# EVK-NORA-W1_SCHEM_0001_NORA_W1_Module.net
KiCad netlist of a schematic drawn in Altium Designer
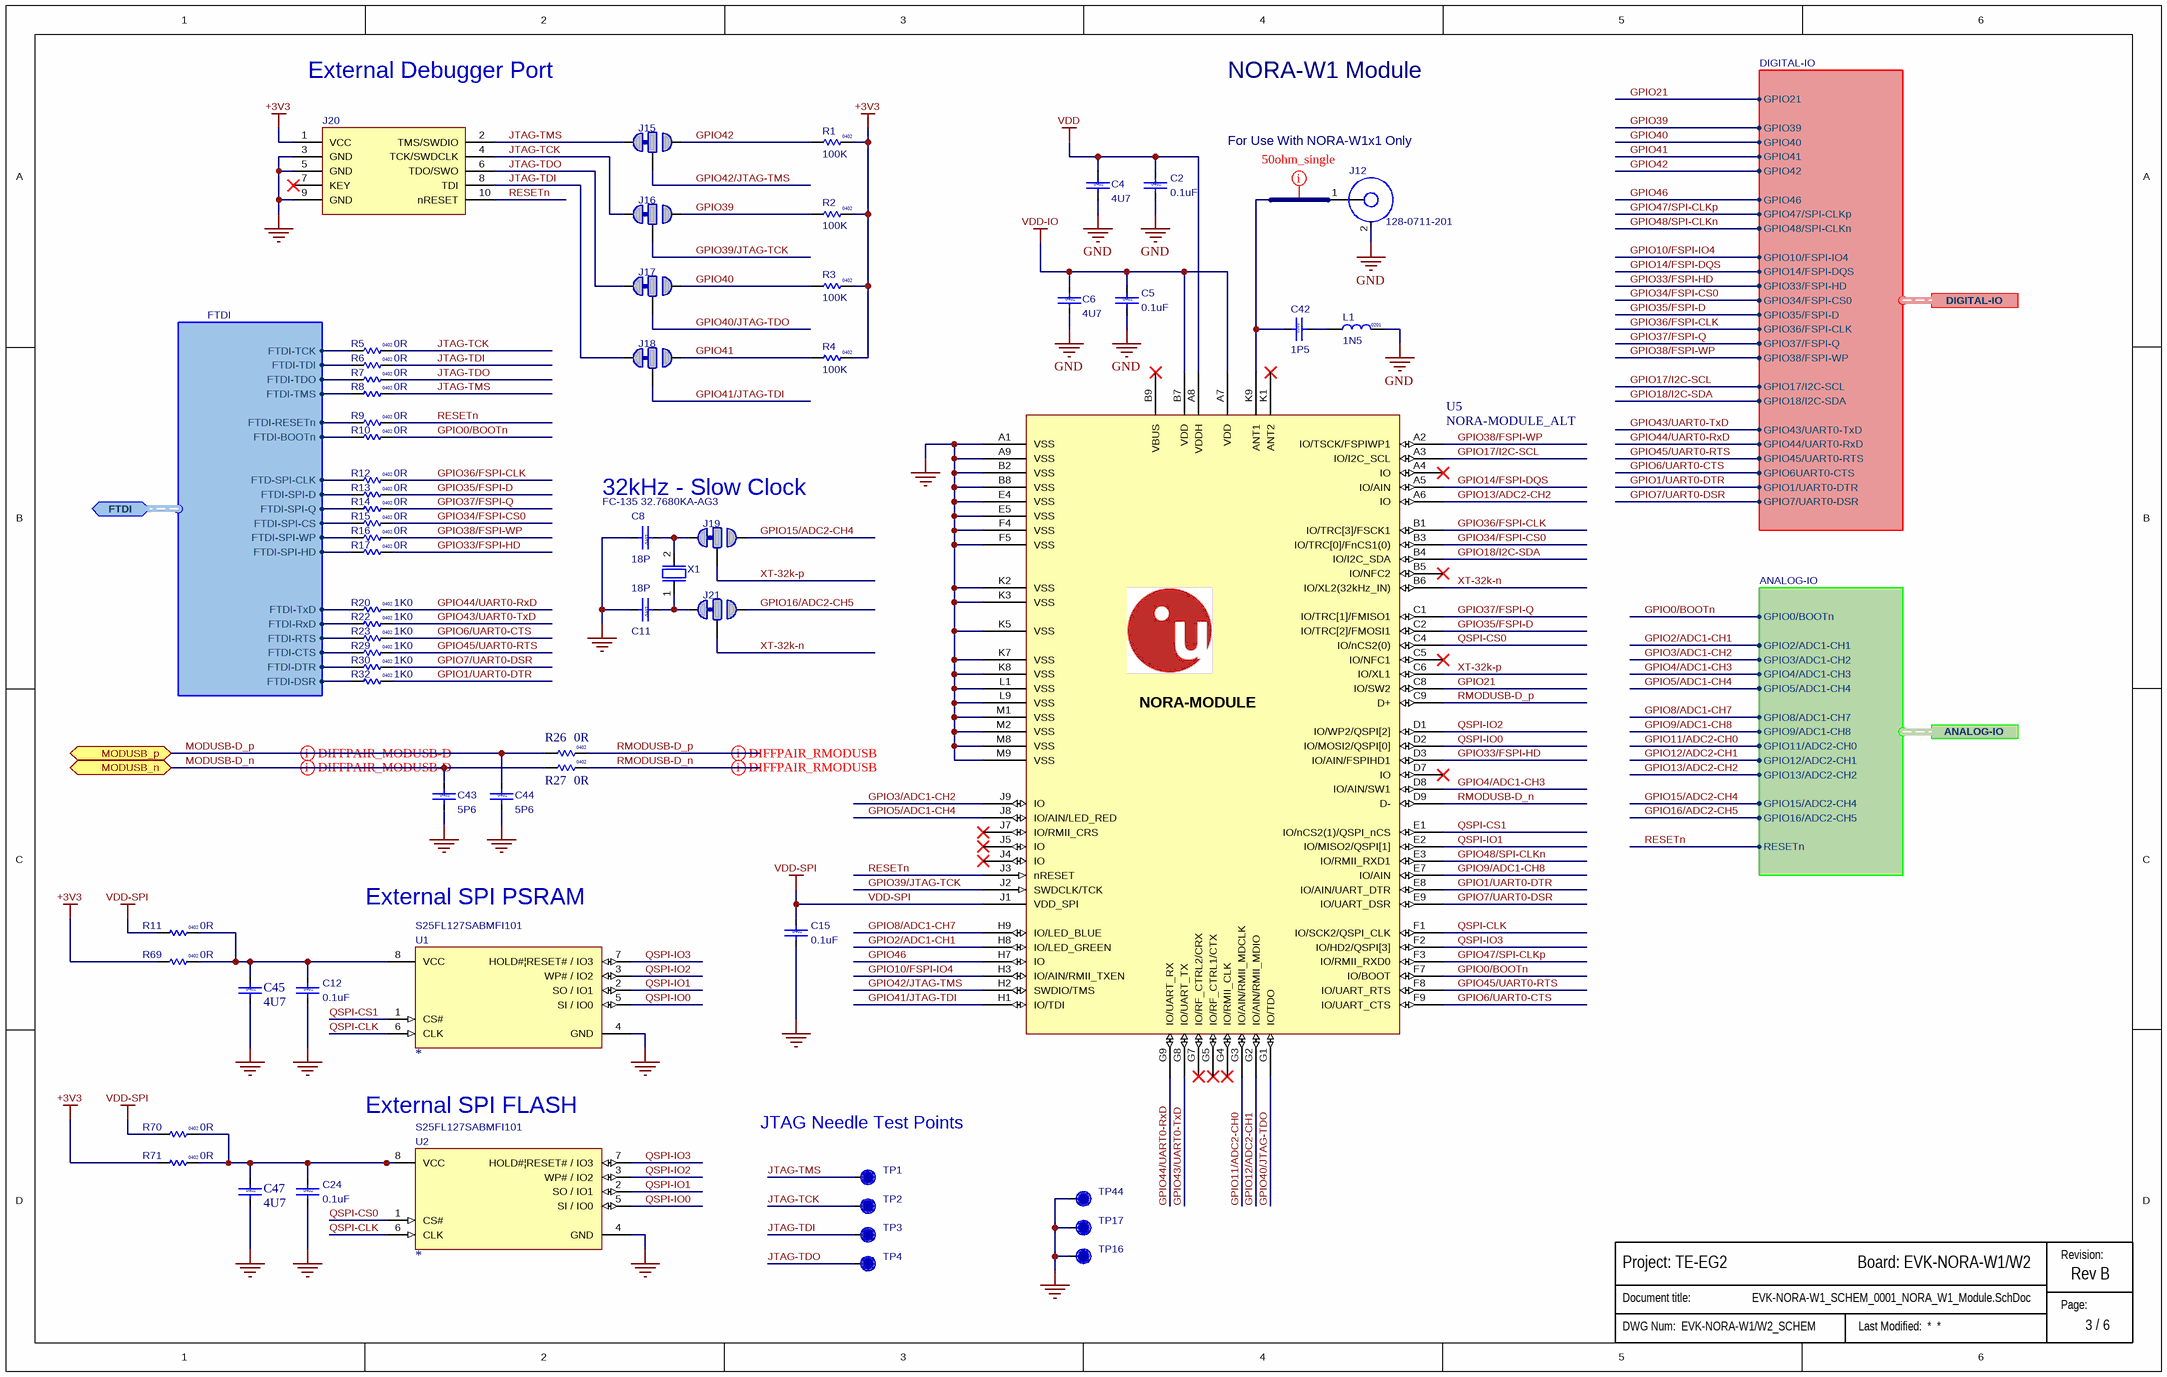
[diagram p0: EVK-NORA-W1_SCHEM_0001_NORA_W1_Module.SchDoc]

(export (version "E")
  (design (tool "Eeschema 10.0.6"))
  (components
    (comp (ref "C2")
      (value "0.1uF")
      (footprint "Cap 0402 HD")
      (description "Cap, Ceramic 0.1uF 10V 10% X5R 0402")
      (fields
        (field (name "SIZE") "0402")
        (field (name "PART NUMBER") "120-00016")
        (field (name "MANUFACTURER") "Murata Electronics North America")
      )
      (libsource (lib "Arena_Parts_DB_Lib") (part "Cap Chip"))
    )
    (comp (ref "C4")
      (value "4U7")
      (footprint "Cap 0402 HD")
      (description "CAP CER X5R 0402 4U7 20% 10V")
      (fields
        (field (name "SIZE") "0402")
        (field (name "PART NUMBER") "UBXH01-0000243")
        (field (name "TOLERANCE") "20%")
        (field (name "EDITOR") "martin.pilik")
        (field (name "RELEASED BY") "fabrice.bret-dibat")
      )
      (libsource (lib "UBX_Parts_DB_Lib") (part "Cap Chip"))
    )
    (comp (ref "C5")
      (value "0.1uF")
      (footprint "Cap 0402 HD")
      (description "Cap, Ceramic 0.1uF 10V 10% X5R 0402")
      (fields
        (field (name "SIZE") "0402")
        (field (name "PART NUMBER") "120-00016")
        (field (name "MANUFACTURER") "Murata Electronics North America")
      )
      (libsource (lib "Arena_Parts_DB_Lib") (part "Cap Chip"))
    )
    (comp (ref "C6")
      (value "4U7")
      (footprint "Cap 0402 HD")
      (description "CAP CER X5R 0402 4U7 20% 10V")
      (fields
        (field (name "SIZE") "0402")
        (field (name "PART NUMBER") "UBXH01-0000243")
        (field (name "TOLERANCE") "20%")
        (field (name "EDITOR") "martin.pilik")
        (field (name "RELEASED BY") "fabrice.bret-dibat")
      )
      (libsource (lib "UBX_Parts_DB_Lib") (part "Cap Chip"))
    )
    (comp (ref "C8")
      (value "18P")
      (footprint "Cap 0402")
      (description "CAP CER C0G 0402 18P 5% 25V")
      (fields
        (field (name "SIZE") "0402")
        (field (name "PART NUMBER") "UBXH01-0004017")
        (field (name "TOLERANCE") "5%")
        (field (name "EDITOR") "doris.zahnd")
        (field (name "RELEASED BY") "daniel.hurni")
      )
      (libsource (lib "UBX_Parts_DB_Lib") (part "Cap Chip"))
    )
    (comp (ref "C11")
      (value "18P")
      (footprint "Cap 0402")
      (description "CAP CER C0G 0402 18P 5% 25V")
      (fields
        (field (name "SIZE") "0402")
        (field (name "PART NUMBER") "UBXH01-0004017")
        (field (name "TOLERANCE") "5%")
        (field (name "EDITOR") "doris.zahnd")
        (field (name "RELEASED BY") "daniel.hurni")
      )
      (libsource (lib "UBX_Parts_DB_Lib") (part "Cap Chip"))
    )
    (comp (ref "C12")
      (value "0.1uF")
      (footprint "Cap 0402 HD")
      (description "Cap, Ceramic 0.1uF 10V 10% X5R 0402")
      (fields
        (field (name "SIZE") "0402")
        (field (name "PART NUMBER") "120-00016")
        (field (name "MANUFACTURER") "Murata Electronics North America")
      )
      (libsource (lib "Arena_Parts_DB_Lib") (part "Cap Chip"))
    )
    (comp (ref "C15")
      (value "0.1uF")
      (footprint "Cap 0402 HD")
      (description "Cap, Ceramic 0.1uF 10V 10% X5R 0402")
      (fields
        (field (name "SIZE") "0402")
        (field (name "PART NUMBER") "120-00016")
        (field (name "MANUFACTURER") "Murata Electronics North America")
      )
      (libsource (lib "Arena_Parts_DB_Lib") (part "Cap Chip"))
    )
    (comp (ref "C24")
      (value "0.1uF")
      (footprint "Cap 0402 HD")
      (description "Cap, Ceramic 0.1uF 10V 10% X5R 0402")
      (fields
        (field (name "SIZE") "0402")
        (field (name "PART NUMBER") "120-00016")
        (field (name "MANUFACTURER") "Murata Electronics North America")
      )
      (libsource (lib "Arena_Parts_DB_Lib") (part "Cap Chip"))
    )
    (comp (ref "C42")
      (value "1P5")
      (footprint "Cap 0201 HD")
      (description "CAP CER C0G 0201 1P5 +/-0.25P 25V")
      (fields
        (field (name "SIZE") "0201")
        (field (name "PART NUMBER") "UBXH01-0012002")
        (field (name "TOLERANCE") "+/-0.25P")
        (field (name "EDITOR") "roland.rust")
        (field (name "RELEASED BY") "roland.rust")
      )
      (libsource (lib "UBX_Parts_DB_Lib") (part "Cap Chip"))
    )
    (comp (ref "C43")
      (value "5P6")
      (footprint "Cap 0402")
      (description "CAP CER C0G 0402 5P6 +/-0.25P 25V")
      (fields
        (field (name "SIZE") "0402")
        (field (name "PART NUMBER") "UBXH01-0004011")
        (field (name "TOLERANCE") "+/-0.25P")
        (field (name "EDITOR") "roland.rust")
        (field (name "RELEASED BY") "roland.rust")
      )
      (libsource (lib "UBX_Parts_DB_Lib") (part "Cap Chip"))
    )
    (comp (ref "C44")
      (value "5P6")
      (footprint "Cap 0402")
      (description "CAP CER C0G 0402 5P6 +/-0.25P 25V")
      (fields
        (field (name "SIZE") "0402")
        (field (name "PART NUMBER") "UBXH01-0004011")
        (field (name "TOLERANCE") "+/-0.25P")
        (field (name "EDITOR") "roland.rust")
        (field (name "RELEASED BY") "roland.rust")
      )
      (libsource (lib "UBX_Parts_DB_Lib") (part "Cap Chip"))
    )
    (comp (ref "C45")
      (value "4U7")
      (footprint "Cap 0402 HD")
      (description "CAP CER X5R 0402 4U7 20% 10V")
      (fields
        (field (name "SIZE") "0402")
        (field (name "PART NUMBER") "UBXH01-0000243")
        (field (name "TOLERANCE") "20%")
        (field (name "EDITOR") "martin.pilik")
        (field (name "RELEASED BY") "fabrice.bret-dibat")
      )
      (libsource (lib "UBX_Parts_DB_Lib") (part "Cap Chip"))
    )
    (comp (ref "C47")
      (value "4U7")
      (footprint "Cap 0402 HD")
      (description "CAP CER X5R 0402 4U7 20% 10V")
      (fields
        (field (name "SIZE") "0402")
        (field (name "PART NUMBER") "UBXH01-0000243")
        (field (name "TOLERANCE") "20%")
        (field (name "EDITOR") "martin.pilik")
        (field (name "RELEASED BY") "fabrice.bret-dibat")
      )
      (libsource (lib "UBX_Parts_DB_Lib") (part "Cap Chip"))
    )
    (comp (ref "J12")
      (value "130-00067")
      (footprint "U.FL_3Pin")
      (description "U.FL jack, SMA 50 ohm, 3 pin, SMT")
      (fields
        (field (name "MANUFACTURER P/N") "128-0711-201")
        (field (name "MANUFACTURER") "Cinch Connectivity")
      )
      (libsource (lib "Arena_Parts_DB_Lib") (part "CON_Coax_2Pin"))
    )
    (comp (ref "J15")
      (value "Solderbridge-OptionDNP")
      (footprint "Solderbridge-Option")
      (description "Solderbridge-Option")
      (fields (field (name "ADDED BY") "Paul B"))
      (libsource (lib "LEGACY_Rigado_AltiumLib") (part "Solderbridge-Option"))
    )
    (comp (ref "J16")
      (value "Solderbridge-OptionDNP")
      (footprint "Solderbridge-Option")
      (description "Solderbridge-Option")
      (fields (field (name "ADDED BY") "Paul B"))
      (libsource (lib "LEGACY_Rigado_AltiumLib") (part "Solderbridge-Option"))
    )
    (comp (ref "J17")
      (value "Solderbridge-OptionDNP")
      (footprint "Solderbridge-Option")
      (description "Solderbridge-Option")
      (fields (field (name "ADDED BY") "Paul B"))
      (libsource (lib "LEGACY_Rigado_AltiumLib") (part "Solderbridge-Option"))
    )
    (comp (ref "J18")
      (value "Solderbridge-OptionDNP")
      (footprint "Solderbridge-Option")
      (description "Solderbridge-Option")
      (fields (field (name "ADDED BY") "Paul B"))
      (libsource (lib "LEGACY_Rigado_AltiumLib") (part "Solderbridge-Option"))
    )
    (comp (ref "J19")
      (value "Solderbridge-OptionDNP")
      (footprint "Solderbridge-Option")
      (description "Solderbridge-Option")
      (fields (field (name "ADDED BY") "Paul B"))
      (libsource (lib "LEGACY_Rigado_AltiumLib") (part "Solderbridge-Option"))
    )
    (comp (ref "J20")
      (value "130-00099")
      (footprint "HDR.050P-10Pin-2x5-SMT_Key")
      (description "Header 0.05\" 10Pin 2Row SMD Black")
      (fields (field (name "MANUFACTURER") "Samtec"))
      (libsource (lib "Arena_Parts_DB_Lib") (part "JTAG-10Pin"))
    )
    (comp (ref "J21")
      (value "Solderbridge-OptionDNP")
      (footprint "Solderbridge-Option")
      (description "Solderbridge-Option")
      (fields (field (name "ADDED BY") "Paul B"))
      (libsource (lib "LEGACY_Rigado_AltiumLib") (part "Solderbridge-Option"))
    )
    (comp (ref "L1")
      (value "1N5")
      (footprint "IND 0201 HD")
      (description "IND MURATA LQP03T_02 0201 1N5 +/-0.1N 600mA")
      (fields
        (field (name "SIZE") "0201")
        (field (name "PART NUMBER") "UBXH09-0000030")
        (field (name "TOLERANCE") "+/-0.1N")
        (field (name "EDITOR") "massimo.pros")
        (field (name "RELEASED BY") "massimo.vlacci")
      )
      (libsource (lib "UBX_Parts_DB_Lib") (part "Ind sm"))
    )
    (comp (ref "R1")
      (value "100K")
      (footprint "RES 0402 HD")
      (description "RES THICK FILM CHIP 0402 100K 5% 100mW")
      (fields
        (field (name "SIZE") "0402")
        (field (name "PART NUMBER") "UBXH18-0008097")
        (field (name "TOLERANCE") "5%")
        (field (name "EDITOR") "roland.rust")
        (field (name "RELEASED BY") "roland.rust")
      )
      (libsource (lib "UBX_Parts_DB_Lib") (part "Res sm"))
    )
    (comp (ref "R2")
      (value "100K")
      (footprint "RES 0402 HD")
      (description "RES THICK FILM CHIP 0402 100K 5% 100mW")
      (fields
        (field (name "SIZE") "0402")
        (field (name "PART NUMBER") "UBXH18-0008097")
        (field (name "TOLERANCE") "5%")
        (field (name "EDITOR") "roland.rust")
        (field (name "RELEASED BY") "roland.rust")
      )
      (libsource (lib "UBX_Parts_DB_Lib") (part "Res sm"))
    )
    (comp (ref "R3")
      (value "100K")
      (footprint "RES 0402 HD")
      (description "RES THICK FILM CHIP 0402 100K 5% 100mW")
      (fields
        (field (name "SIZE") "0402")
        (field (name "PART NUMBER") "UBXH18-0008097")
        (field (name "TOLERANCE") "5%")
        (field (name "EDITOR") "roland.rust")
        (field (name "RELEASED BY") "roland.rust")
      )
      (libsource (lib "UBX_Parts_DB_Lib") (part "Res sm"))
    )
    (comp (ref "R4")
      (value "100K")
      (footprint "RES 0402 HD")
      (description "RES THICK FILM CHIP 0402 100K 5% 100mW")
      (fields
        (field (name "SIZE") "0402")
        (field (name "PART NUMBER") "UBXH18-0008097")
        (field (name "TOLERANCE") "5%")
        (field (name "EDITOR") "roland.rust")
        (field (name "RELEASED BY") "roland.rust")
      )
      (libsource (lib "UBX_Parts_DB_Lib") (part "Res sm"))
    )
    (comp (ref "R5")
      (value "0R")
      (footprint "RES 0402 HD")
      (description "RES THICK FILM CHIP 0402 0R 0 100mW")
      (fields
        (field (name "SIZE") "0402")
        (field (name "PART NUMBER") "UBXH18-0003002")
        (field (name "TOLERANCE") "0")
        (field (name "EDITOR") "charlotte.biber")
        (field (name "RELEASED BY") "peter.mueller")
      )
      (libsource (lib "UBX_Parts_DB_Lib") (part "Res sm"))
    )
    (comp (ref "R6")
      (value "0R")
      (footprint "RES 0402 HD")
      (description "RES THICK FILM CHIP 0402 0R 0 100mW")
      (fields
        (field (name "SIZE") "0402")
        (field (name "PART NUMBER") "UBXH18-0003002")
        (field (name "TOLERANCE") "0")
        (field (name "EDITOR") "charlotte.biber")
        (field (name "RELEASED BY") "peter.mueller")
      )
      (libsource (lib "UBX_Parts_DB_Lib") (part "Res sm"))
    )
    (comp (ref "R7")
      (value "0R")
      (footprint "RES 0402 HD")
      (description "RES THICK FILM CHIP 0402 0R 0 100mW")
      (fields
        (field (name "SIZE") "0402")
        (field (name "PART NUMBER") "UBXH18-0003002")
        (field (name "TOLERANCE") "0")
        (field (name "EDITOR") "charlotte.biber")
        (field (name "RELEASED BY") "peter.mueller")
      )
      (libsource (lib "UBX_Parts_DB_Lib") (part "Res sm"))
    )
    (comp (ref "R8")
      (value "0R")
      (footprint "RES 0402 HD")
      (description "RES THICK FILM CHIP 0402 0R 0 100mW")
      (fields
        (field (name "SIZE") "0402")
        (field (name "PART NUMBER") "UBXH18-0003002")
        (field (name "TOLERANCE") "0")
        (field (name "EDITOR") "charlotte.biber")
        (field (name "RELEASED BY") "peter.mueller")
      )
      (libsource (lib "UBX_Parts_DB_Lib") (part "Res sm"))
    )
    (comp (ref "R9")
      (value "0R")
      (footprint "RES 0402 HD")
      (description "RES THICK FILM CHIP 0402 0R 0 100mW")
      (fields
        (field (name "SIZE") "0402")
        (field (name "PART NUMBER") "UBXH18-0003002")
        (field (name "TOLERANCE") "0")
        (field (name "EDITOR") "charlotte.biber")
        (field (name "RELEASED BY") "peter.mueller")
      )
      (libsource (lib "UBX_Parts_DB_Lib") (part "Res sm"))
    )
    (comp (ref "R10")
      (value "0R")
      (footprint "RES 0402 HD")
      (description "RES THICK FILM CHIP 0402 0R 0 100mW")
      (fields
        (field (name "SIZE") "0402")
        (field (name "PART NUMBER") "UBXH18-0003002")
        (field (name "TOLERANCE") "0")
        (field (name "EDITOR") "charlotte.biber")
        (field (name "RELEASED BY") "peter.mueller")
      )
      (libsource (lib "UBX_Parts_DB_Lib") (part "Res sm"))
    )
    (comp (ref "R11")
      (value "0R")
      (footprint "RES 0402 HD")
      (description "RES THICK FILM CHIP 0402 0R 0 100mW")
      (fields
        (field (name "SIZE") "0402")
        (field (name "PART NUMBER") "UBXH18-0003002")
        (field (name "TOLERANCE") "0")
        (field (name "EDITOR") "charlotte.biber")
        (field (name "RELEASED BY") "peter.mueller")
      )
      (libsource (lib "UBX_Parts_DB_Lib") (part "Res sm"))
    )
    (comp (ref "R12")
      (value "0R")
      (footprint "RES 0402 HD")
      (description "RES THICK FILM CHIP 0402 0R 0 100mW")
      (fields
        (field (name "SIZE") "0402")
        (field (name "PART NUMBER") "UBXH18-0003002")
        (field (name "TOLERANCE") "0")
        (field (name "EDITOR") "charlotte.biber")
        (field (name "RELEASED BY") "peter.mueller")
      )
      (libsource (lib "UBX_Parts_DB_Lib") (part "Res sm"))
    )
    (comp (ref "R13")
      (value "0R")
      (footprint "RES 0402 HD")
      (description "RES THICK FILM CHIP 0402 0R 0 100mW")
      (fields
        (field (name "SIZE") "0402")
        (field (name "PART NUMBER") "UBXH18-0003002")
        (field (name "TOLERANCE") "0")
        (field (name "EDITOR") "charlotte.biber")
        (field (name "RELEASED BY") "peter.mueller")
      )
      (libsource (lib "UBX_Parts_DB_Lib") (part "Res sm"))
    )
    (comp (ref "R14")
      (value "0R")
      (footprint "RES 0402 HD")
      (description "RES THICK FILM CHIP 0402 0R 0 100mW")
      (fields
        (field (name "SIZE") "0402")
        (field (name "PART NUMBER") "UBXH18-0003002")
        (field (name "TOLERANCE") "0")
        (field (name "EDITOR") "charlotte.biber")
        (field (name "RELEASED BY") "peter.mueller")
      )
      (libsource (lib "UBX_Parts_DB_Lib") (part "Res sm"))
    )
    (comp (ref "R15")
      (value "0R")
      (footprint "RES 0402 HD")
      (description "RES THICK FILM CHIP 0402 0R 0 100mW")
      (fields
        (field (name "SIZE") "0402")
        (field (name "PART NUMBER") "UBXH18-0003002")
        (field (name "TOLERANCE") "0")
        (field (name "EDITOR") "charlotte.biber")
        (field (name "RELEASED BY") "peter.mueller")
      )
      (libsource (lib "UBX_Parts_DB_Lib") (part "Res sm"))
    )
    (comp (ref "R16")
      (value "0R")
      (footprint "RES 0402 HD")
      (description "RES THICK FILM CHIP 0402 0R 0 100mW")
      (fields
        (field (name "SIZE") "0402")
        (field (name "PART NUMBER") "UBXH18-0003002")
        (field (name "TOLERANCE") "0")
        (field (name "EDITOR") "charlotte.biber")
        (field (name "RELEASED BY") "peter.mueller")
      )
      (libsource (lib "UBX_Parts_DB_Lib") (part "Res sm"))
    )
    (comp (ref "R17")
      (value "0R")
      (footprint "RES 0402 HD")
      (description "RES THICK FILM CHIP 0402 0R 0 100mW")
      (fields
        (field (name "SIZE") "0402")
        (field (name "PART NUMBER") "UBXH18-0003002")
        (field (name "TOLERANCE") "0")
        (field (name "EDITOR") "charlotte.biber")
        (field (name "RELEASED BY") "peter.mueller")
      )
      (libsource (lib "UBX_Parts_DB_Lib") (part "Res sm"))
    )
    (comp (ref "R20")
      (value "1K0")
      (footprint "RES 0402 HD")
      (description "RES THICK FILM CHIP 0402 1K0 5% 100mW")
      (fields
        (field (name "SIZE") "0402")
        (field (name "PART NUMBER") "UBXH18-0008049")
        (field (name "TOLERANCE") "5%")
        (field (name "EDITOR") "roland.rust")
        (field (name "RELEASED BY") "roland.rust")
      )
      (libsource (lib "UBX_Parts_DB_Lib") (part "Res sm"))
    )
    (comp (ref "R22")
      (value "1K0")
      (footprint "RES 0402 HD")
      (description "RES THICK FILM CHIP 0402 1K0 5% 100mW")
      (fields
        (field (name "SIZE") "0402")
        (field (name "PART NUMBER") "UBXH18-0008049")
        (field (name "TOLERANCE") "5%")
        (field (name "EDITOR") "roland.rust")
        (field (name "RELEASED BY") "roland.rust")
      )
      (libsource (lib "UBX_Parts_DB_Lib") (part "Res sm"))
    )
    (comp (ref "R23")
      (value "1K0")
      (footprint "RES 0402 HD")
      (description "RES THICK FILM CHIP 0402 1K0 5% 100mW")
      (fields
        (field (name "SIZE") "0402")
        (field (name "PART NUMBER") "UBXH18-0008049")
        (field (name "TOLERANCE") "5%")
        (field (name "EDITOR") "roland.rust")
        (field (name "RELEASED BY") "roland.rust")
      )
      (libsource (lib "UBX_Parts_DB_Lib") (part "Res sm"))
    )
    (comp (ref "R26")
      (value "0R")
      (footprint "RES 0402 HD")
      (description "RES THICK FILM CHIP 0402 0R 0 100mW")
      (fields
        (field (name "SIZE") "0402")
        (field (name "PART NUMBER") "UBXH18-0003002")
        (field (name "TOLERANCE") "0")
        (field (name "EDITOR") "charlotte.biber")
        (field (name "RELEASED BY") "peter.mueller")
      )
      (libsource (lib "UBX_Parts_DB_Lib") (part "Res sm"))
    )
    (comp (ref "R27")
      (value "0R")
      (footprint "RES 0402 HD")
      (description "RES THICK FILM CHIP 0402 0R 0 100mW")
      (fields
        (field (name "SIZE") "0402")
        (field (name "PART NUMBER") "UBXH18-0003002")
        (field (name "TOLERANCE") "0")
        (field (name "EDITOR") "charlotte.biber")
        (field (name "RELEASED BY") "peter.mueller")
      )
      (libsource (lib "UBX_Parts_DB_Lib") (part "Res sm"))
    )
    (comp (ref "R29")
      (value "1K0")
      (footprint "RES 0402 HD")
      (description "RES THICK FILM CHIP 0402 1K0 5% 100mW")
      (fields
        (field (name "SIZE") "0402")
        (field (name "PART NUMBER") "UBXH18-0008049")
        (field (name "TOLERANCE") "5%")
        (field (name "EDITOR") "roland.rust")
        (field (name "RELEASED BY") "roland.rust")
      )
      (libsource (lib "UBX_Parts_DB_Lib") (part "Res sm"))
    )
    (comp (ref "R30")
      (value "1K0")
      (footprint "RES 0402 HD")
      (description "RES THICK FILM CHIP 0402 1K0 5% 100mW")
      (fields
        (field (name "SIZE") "0402")
        (field (name "PART NUMBER") "UBXH18-0008049")
        (field (name "TOLERANCE") "5%")
        (field (name "EDITOR") "roland.rust")
        (field (name "RELEASED BY") "roland.rust")
      )
      (libsource (lib "UBX_Parts_DB_Lib") (part "Res sm"))
    )
    (comp (ref "R32")
      (value "1K0")
      (footprint "RES 0402 HD")
      (description "RES THICK FILM CHIP 0402 1K0 5% 100mW")
      (fields
        (field (name "SIZE") "0402")
        (field (name "PART NUMBER") "UBXH18-0008049")
        (field (name "TOLERANCE") "5%")
        (field (name "EDITOR") "roland.rust")
        (field (name "RELEASED BY") "roland.rust")
      )
      (libsource (lib "UBX_Parts_DB_Lib") (part "Res sm"))
    )
    (comp (ref "R69")
      (value "0R")
      (footprint "RES 0402 HD")
      (description "RES THICK FILM CHIP 0402 0R 0 100mW")
      (fields
        (field (name "SIZE") "0402")
        (field (name "PART NUMBER") "UBXH18-0003002")
        (field (name "TOLERANCE") "0")
        (field (name "EDITOR") "charlotte.biber")
        (field (name "RELEASED BY") "peter.mueller")
      )
      (libsource (lib "UBX_Parts_DB_Lib") (part "Res sm"))
    )
    (comp (ref "R70")
      (value "0R")
      (footprint "RES 0402 HD")
      (description "RES THICK FILM CHIP 0402 0R 0 100mW")
      (fields
        (field (name "SIZE") "0402")
        (field (name "PART NUMBER") "UBXH18-0003002")
        (field (name "TOLERANCE") "0")
        (field (name "EDITOR") "charlotte.biber")
        (field (name "RELEASED BY") "peter.mueller")
      )
      (libsource (lib "UBX_Parts_DB_Lib") (part "Res sm"))
    )
    (comp (ref "R71")
      (value "0R")
      (footprint "RES 0402 HD")
      (description "RES THICK FILM CHIP 0402 0R 0 100mW")
      (fields
        (field (name "SIZE") "0402")
        (field (name "PART NUMBER") "UBXH18-0003002")
        (field (name "TOLERANCE") "0")
        (field (name "EDITOR") "charlotte.biber")
        (field (name "RELEASED BY") "peter.mueller")
      )
      (libsource (lib "UBX_Parts_DB_Lib") (part "Res sm"))
    )
    (comp (ref "TP1")
      (value "TP")
      (footprint "TP10R")
      (description "Testpoint, Round 1.0mm Dia")
      (fields
        (field (name "PART NUMBER") "TP10R")
        (field (name "ADDED BY") "Jeremy D")
        (field (name "CHECKED BY") "Paul B")
      )
      (libsource (lib "LEGACY_Rigado_AltiumLib") (part "TP_R"))
    )
    (comp (ref "TP2")
      (value "TP")
      (footprint "TP10R")
      (description "Testpoint, Round 1.0mm Dia")
      (fields
        (field (name "PART NUMBER") "TP10R")
        (field (name "ADDED BY") "Jeremy D")
        (field (name "CHECKED BY") "Paul B")
      )
      (libsource (lib "LEGACY_Rigado_AltiumLib") (part "TP_R"))
    )
    (comp (ref "TP3")
      (value "TP")
      (footprint "TP10R")
      (description "Testpoint, Round 1.0mm Dia")
      (fields
        (field (name "PART NUMBER") "TP10R")
        (field (name "ADDED BY") "Jeremy D")
        (field (name "CHECKED BY") "Paul B")
      )
      (libsource (lib "LEGACY_Rigado_AltiumLib") (part "TP_R"))
    )
    (comp (ref "TP4")
      (value "TP")
      (footprint "TP10R")
      (description "Testpoint, Round 1.0mm Dia")
      (fields
        (field (name "PART NUMBER") "TP10R")
        (field (name "ADDED BY") "Jeremy D")
        (field (name "CHECKED BY") "Paul B")
      )
      (libsource (lib "LEGACY_Rigado_AltiumLib") (part "TP_R"))
    )
    (comp (ref "TP16")
      (value "TP")
      (footprint "TP10R")
      (description "Testpoint, Round 1.0mm Dia")
      (fields
        (field (name "PART NUMBER") "TP10R")
        (field (name "ADDED BY") "Jeremy D")
        (field (name "CHECKED BY") "Paul B")
      )
      (libsource (lib "LEGACY_Rigado_AltiumLib") (part "TP_R"))
    )
    (comp (ref "TP17")
      (value "TP")
      (footprint "TP10R")
      (description "Testpoint, Round 1.0mm Dia")
      (fields
        (field (name "PART NUMBER") "TP10R")
        (field (name "ADDED BY") "Jeremy D")
        (field (name "CHECKED BY") "Paul B")
      )
      (libsource (lib "LEGACY_Rigado_AltiumLib") (part "TP_R"))
    )
    (comp (ref "TP44")
      (value "TP")
      (footprint "TP10R")
      (description "Testpoint, Round 1.0mm Dia")
      (fields
        (field (name "PART NUMBER") "TP10R")
        (field (name "ADDED BY") "Jeremy D")
        (field (name "CHECKED BY") "Paul B")
      )
      (libsource (lib "LEGACY_Rigado_AltiumLib") (part "TP_R"))
    )
    (comp (ref "U1")
      (value "240-00017")
      (footprint "SOIC-8W")
      (description "IC, Flash 128MBIT, 108MHz, 8SOIC")
      (fields
        (field (name "MANUFACTURER P/N") "*")
        (field (name "MANUFACTURER PART NUMBER 1") "S25FL127SABMFI101")
        (field (name "VOLTAGE") "3.6V")
      )
      (libsource (lib "Arena_Parts_DB_Lib") (part "SPI_Flash_Memory_8Pin"))
    )
    (comp (ref "U2")
      (value "240-00017")
      (footprint "SOIC-8W")
      (description "IC, Flash 128MBIT, 108MHz, 8SOIC")
      (fields
        (field (name "MANUFACTURER P/N") "*")
        (field (name "MANUFACTURER PART NUMBER 1") "S25FL127SABMFI101")
        (field (name "VOLTAGE") "3.6V")
      )
      (libsource (lib "Arena_Parts_DB_Lib") (part "SPI_Flash_Memory_8Pin"))
    )
    (comp (ref "U5")
      (value "NORA-MODULE_ALT")
      (footprint "NORA:NORA_LGA82R_1430X1040X180_ANT")
      (description "u-blox NORA module generic symbol for use within module designs - alternate version")
      (fields (field (name "PART NUMBER") "NORA") (field (name "MANUFACTURER") "u-blox"))
      (libsource (lib "NORA") (part "NORA-MODULE_ALT"))
    )
    (comp (ref "X1")
      (value "100-00005")
      (footprint "XTAL_3215")
      (description "XTAL, 2Pin, 32.768kHz, 7pF 20ppm")
      (fields (field (name "MANUFACTURER P/N") "FC-135 32.7680KA-AG3") (field (name "MANUFACTURER") "Epson"))
      (libsource (lib "Arena_Parts_DB_Lib") (part "XTAL_2Pin"))
    )
  )
  (nets
    (net (code "4") (name "+3V3") (class "Default")
      (node (ref "J20") (pin "1") (pinfunction "VCC_1") (pintype "passive"))
      (node (ref "R1") (pin "2") (pinfunction "2_2") (pintype "passive"))
      (node (ref "R2") (pin "2") (pinfunction "2_2") (pintype "passive"))
      (node (ref "R3") (pin "2") (pinfunction "2_2") (pintype "passive"))
      (node (ref "R4") (pin "2") (pinfunction "2_2") (pintype "passive"))
      (node (ref "R69") (pin "1") (pinfunction "1_1") (pintype "passive"))
      (node (ref "R71") (pin "1") (pinfunction "1_1") (pintype "passive"))
    )
    (net (code "5") (name "/FTD-SPI-CLK") (class "Default")
      (node (ref "R12") (pin "1") (pinfunction "1_1") (pintype "passive"))
    )
    (net (code "6") (name "/FTDI-BOOTn") (class "Default")
      (node (ref "R10") (pin "1") (pinfunction "1_1") (pintype "passive"))
    )
    (net (code "7") (name "/FTDI-CTS") (class "Default")
      (node (ref "R29") (pin "1") (pinfunction "1_1") (pintype "passive"))
    )
    (net (code "8") (name "/FTDI-DSR") (class "Default")
      (node (ref "R32") (pin "1") (pinfunction "1_1") (pintype "passive"))
    )
    (net (code "9") (name "/FTDI-DTR") (class "Default")
      (node (ref "R30") (pin "1") (pinfunction "1_1") (pintype "passive"))
    )
    (net (code "10") (name "/FTDI-RESETn") (class "Default")
      (node (ref "R9") (pin "1") (pinfunction "1_1") (pintype "passive"))
    )
    (net (code "11") (name "/FTDI-RTS") (class "Default")
      (node (ref "R23") (pin "1") (pinfunction "1_1") (pintype "passive"))
    )
    (net (code "12") (name "/FTDI-RxD") (class "Default")
      (node (ref "R22") (pin "1") (pinfunction "1_1") (pintype "passive"))
    )
    (net (code "13") (name "/FTDI-SPI-CS") (class "Default")
      (node (ref "R15") (pin "1") (pinfunction "1_1") (pintype "passive"))
    )
    (net (code "14") (name "/FTDI-SPI-D") (class "Default")
      (node (ref "R13") (pin "1") (pinfunction "1_1") (pintype "passive"))
    )
    (net (code "15") (name "/FTDI-SPI-HD") (class "Default")
      (node (ref "R17") (pin "1") (pinfunction "1_1") (pintype "passive"))
    )
    (net (code "16") (name "/FTDI-SPI-Q") (class "Default")
      (node (ref "R14") (pin "1") (pinfunction "1_1") (pintype "passive"))
    )
    (net (code "17") (name "/FTDI-SPI-WP") (class "Default")
      (node (ref "R16") (pin "1") (pinfunction "1_1") (pintype "passive"))
    )
    (net (code "18") (name "/FTDI-TCK") (class "Default")
      (node (ref "R5") (pin "1") (pinfunction "1_1") (pintype "passive"))
    )
    (net (code "19") (name "/FTDI-TDI") (class "Default")
      (node (ref "R6") (pin "1") (pinfunction "1_1") (pintype "passive"))
    )
    (net (code "20") (name "/FTDI-TDO") (class "Default")
      (node (ref "R7") (pin "1") (pinfunction "1_1") (pintype "passive"))
    )
    (net (code "21") (name "/FTDI-TMS") (class "Default")
      (node (ref "R8") (pin "1") (pinfunction "1_1") (pintype "passive"))
    )
    (net (code "22") (name "/FTDI-TxD") (class "Default")
      (node (ref "R20") (pin "1") (pinfunction "1_1") (pintype "passive"))
    )
    (net (code "23") (name "/GPIO0{slash}BOOTn") (class "Default")
      (node (ref "R10") (pin "2") (pinfunction "2_2") (pintype "passive"))
      (node (ref "U5") (pin "F7") (pinfunction "IO/BOOT_F7") (pintype "bidirectional"))
    )
    (net (code "24") (name "/GPIO1{slash}UART0-DTR") (class "Default")
      (node (ref "R32") (pin "2") (pinfunction "2_2") (pintype "passive"))
      (node (ref "U5") (pin "E8") (pinfunction "IO/AIN/UART_DTR_E8") (pintype "bidirectional"))
    )
    (net (code "25") (name "/GPIO2{slash}ADC1-CH1") (class "Default")
      (node (ref "U5") (pin "H8") (pinfunction "IO/LED_GREEN_H8") (pintype "bidirectional"))
    )
    (net (code "26") (name "/GPIO3{slash}ADC1-CH2") (class "Default")
      (node (ref "U5") (pin "J9") (pinfunction "IO_J9") (pintype "bidirectional"))
    )
    (net (code "27") (name "/GPIO4{slash}ADC1-CH3") (class "Default")
      (node (ref "U5") (pin "D8") (pinfunction "IO/AIN/SW1_D8") (pintype "bidirectional"))
    )
    (net (code "28") (name "/GPIO5{slash}ADC1-CH4") (class "Default")
      (node (ref "U5") (pin "J8") (pinfunction "IO/AIN/LED_RED_J8") (pintype "bidirectional"))
    )
    (net (code "29") (name "/GPIO6{slash}UART0-CTS") (class "Default")
      (node (ref "R23") (pin "2") (pinfunction "2_2") (pintype "passive"))
      (node (ref "U5") (pin "F9") (pinfunction "IO/UART_CTS_F9") (pintype "bidirectional"))
    )
    (net (code "30") (name "/GPIO7{slash}UART0-DSR") (class "Default")
      (node (ref "R30") (pin "2") (pinfunction "2_2") (pintype "passive"))
      (node (ref "U5") (pin "E9") (pinfunction "IO/UART_DSR_E9") (pintype "bidirectional"))
    )
    (net (code "31") (name "/GPIO8{slash}ADC1-CH7") (class "Default")
      (node (ref "U5") (pin "H9") (pinfunction "IO/LED_BLUE_H9") (pintype "bidirectional"))
    )
    (net (code "32") (name "/GPIO9{slash}ADC1-CH8") (class "Default")
      (node (ref "U5") (pin "E7") (pinfunction "IO/AIN_E7") (pintype "bidirectional"))
    )
    (net (code "33") (name "/GPIO10{slash}FSPI-IO4") (class "Default")
      (node (ref "U5") (pin "H3") (pinfunction "IO/AIN/RMII_TXEN_H3") (pintype "bidirectional"))
    )
    (net (code "34") (name "/GPIO11{slash}ADC2-CH0") (class "Default")
      (node (ref "U5") (pin "G3") (pinfunction "IO/AIN/RMII_MDCLK_G3") (pintype "bidirectional"))
    )
    (net (code "35") (name "/GPIO12{slash}ADC2-CH1") (class "Default")
      (node (ref "U5") (pin "G2") (pinfunction "IO/AIN/RMII_MDIO_G2") (pintype "bidirectional"))
    )
    (net (code "36") (name "/GPIO13{slash}ADC2-CH2") (class "Default")
      (node (ref "U5") (pin "A6") (pinfunction "IO_A6") (pintype "bidirectional"))
    )
    (net (code "37") (name "/GPIO14{slash}FSPI-DQS") (class "Default")
      (node (ref "U5") (pin "A5") (pinfunction "IO/AIN_A5") (pintype "bidirectional"))
    )
    (net (code "38") (name "/GPIO15{slash}ADC2-CH4") (class "Default")
      (node (ref "J19") (pin "3") (pinfunction "3_3") (pintype "passive"))
    )
    (net (code "39") (name "/GPIO16{slash}ADC2-CH5") (class "Default")
      (node (ref "J21") (pin "3") (pinfunction "3_3") (pintype "passive"))
    )
    (net (code "40") (name "/GPIO17{slash}I2C-SCL") (class "Default")
      (node (ref "U5") (pin "A3") (pinfunction "IO/I2C_SCL_A3") (pintype "bidirectional"))
    )
    (net (code "41") (name "/GPIO18{slash}I2C-SDA") (class "Default")
      (node (ref "U5") (pin "B4") (pinfunction "IO/I2C_SDA_B4") (pintype "bidirectional"))
    )
    (net (code "42") (name "/GPIO21") (class "Default")
      (node (ref "U5") (pin "C8") (pinfunction "IO/SW2_C8") (pintype "bidirectional"))
    )
    (net (code "43") (name "/GPIO33{slash}FSPI-HD") (class "Default")
      (node (ref "R17") (pin "2") (pinfunction "2_2") (pintype "passive"))
      (node (ref "U5") (pin "D3") (pinfunction "IO/AIN/FSPIHD1_D3") (pintype "bidirectional"))
    )
    (net (code "44") (name "/GPIO34{slash}FSPI-CS0") (class "Default")
      (node (ref "R15") (pin "2") (pinfunction "2_2") (pintype "passive"))
      (node (ref "U5") (pin "B3") (pinfunction "IO/TRC[0]/FnCS1(0)_B3") (pintype "bidirectional"))
    )
    (net (code "45") (name "/GPIO35{slash}FSPI-D") (class "Default")
      (node (ref "R13") (pin "2") (pinfunction "2_2") (pintype "passive"))
      (node (ref "U5") (pin "C2") (pinfunction "IO/TRC[2]/FMOSI1_C2") (pintype "bidirectional"))
    )
    (net (code "46") (name "/GPIO36{slash}FSPI-CLK") (class "Default")
      (node (ref "R12") (pin "2") (pinfunction "2_2") (pintype "passive"))
      (node (ref "U5") (pin "B1") (pinfunction "IO/TRC[3]/FSCK1_B1") (pintype "bidirectional"))
    )
    (net (code "47") (name "/GPIO37{slash}FSPI-Q") (class "Default")
      (node (ref "R14") (pin "2") (pinfunction "2_2") (pintype "passive"))
      (node (ref "U5") (pin "C1") (pinfunction "IO/TRC[1]/FMISO1_C1") (pintype "bidirectional"))
    )
    (net (code "48") (name "/GPIO38{slash}FSPI-WP") (class "Default")
      (node (ref "R16") (pin "2") (pinfunction "2_2") (pintype "passive"))
      (node (ref "U5") (pin "A2") (pinfunction "IO/TSCK/FSPIWP1_A2") (pintype "bidirectional"))
    )
    (net (code "49") (name "/GPIO39") (class "Default")
      (node (ref "J16") (pin "3") (pinfunction "3_3") (pintype "passive"))
      (node (ref "R2") (pin "1") (pinfunction "1_1") (pintype "passive"))
    )
    (net (code "50") (name "/GPIO39{slash}JTAG-TCK") (class "Default")
      (node (ref "J16") (pin "2") (pinfunction "2_2") (pintype "passive"))
      (node (ref "U5") (pin "J2") (pinfunction "SWDCLK/TCK_J2") (pintype "input"))
    )
    (net (code "51") (name "/GPIO40") (class "Default")
      (node (ref "J17") (pin "3") (pinfunction "3_3") (pintype "passive"))
      (node (ref "R3") (pin "1") (pinfunction "1_1") (pintype "passive"))
    )
    (net (code "52") (name "/GPIO40{slash}JTAG-TDO") (class "Default")
      (node (ref "J17") (pin "2") (pinfunction "2_2") (pintype "passive"))
      (node (ref "U5") (pin "G1") (pinfunction "IO/TDO_G1") (pintype "bidirectional"))
    )
    (net (code "53") (name "/GPIO41") (class "Default")
      (node (ref "J18") (pin "3") (pinfunction "3_3") (pintype "passive"))
      (node (ref "R4") (pin "1") (pinfunction "1_1") (pintype "passive"))
    )
    (net (code "54") (name "/GPIO41{slash}JTAG-TDI") (class "Default")
      (node (ref "J18") (pin "2") (pinfunction "2_2") (pintype "passive"))
      (node (ref "U5") (pin "H1") (pinfunction "IO/TDI_H1") (pintype "bidirectional"))
    )
    (net (code "55") (name "/GPIO42") (class "Default")
      (node (ref "J15") (pin "3") (pinfunction "3_3") (pintype "passive"))
      (node (ref "R1") (pin "1") (pinfunction "1_1") (pintype "passive"))
    )
    (net (code "56") (name "/GPIO42{slash}JTAG-TMS") (class "Default")
      (node (ref "J15") (pin "2") (pinfunction "2_2") (pintype "passive"))
      (node (ref "U5") (pin "H2") (pinfunction "SWDIO/TMS_H2") (pintype "bidirectional"))
    )
    (net (code "57") (name "/GPIO43{slash}UART0-TxD") (class "Default")
      (node (ref "R22") (pin "2") (pinfunction "2_2") (pintype "passive"))
      (node (ref "U5") (pin "G8") (pinfunction "IO/UART_TX_G8") (pintype "bidirectional"))
    )
    (net (code "58") (name "/GPIO44{slash}UART0-RxD") (class "Default")
      (node (ref "R20") (pin "2") (pinfunction "2_2") (pintype "passive"))
      (node (ref "U5") (pin "G9") (pinfunction "IO/UART_RX_G9") (pintype "bidirectional"))
    )
    (net (code "59") (name "/GPIO45{slash}UART0-RTS") (class "Default")
      (node (ref "R29") (pin "2") (pinfunction "2_2") (pintype "passive"))
      (node (ref "U5") (pin "F8") (pinfunction "IO/UART_RTS_F8") (pintype "bidirectional"))
    )
    (net (code "60") (name "/GPIO46") (class "Default")
      (node (ref "U5") (pin "H7") (pinfunction "IO_H7") (pintype "bidirectional"))
    )
    (net (code "61") (name "/GPIO47{slash}SPI-CLKp") (class "Default")
      (node (ref "U5") (pin "F3") (pinfunction "IO/RMII_RXD0_F3") (pintype "bidirectional"))
    )
    (net (code "62") (name "/GPIO48{slash}SPI-CLKn") (class "Default")
      (node (ref "U5") (pin "E3") (pinfunction "IO/RMII_RXD1_E3") (pintype "bidirectional"))
    )
    (net (code "63") (name "/JTAG-TCK") (class "Default")
      (node (ref "J16") (pin "1") (pinfunction "1_1") (pintype "passive"))
      (node (ref "J20") (pin "4") (pinfunction "TCK/SWDCLK_4") (pintype "passive"))
      (node (ref "R5") (pin "2") (pinfunction "2_2") (pintype "passive"))
      (node (ref "TP2") (pin "1") (pintype "passive"))
    )
    (net (code "64") (name "/JTAG-TDI") (class "Default")
      (node (ref "J18") (pin "1") (pinfunction "1_1") (pintype "passive"))
      (node (ref "J20") (pin "8") (pinfunction "TDI_8") (pintype "passive"))
      (node (ref "R6") (pin "2") (pinfunction "2_2") (pintype "passive"))
      (node (ref "TP3") (pin "1") (pintype "passive"))
    )
    (net (code "65") (name "/JTAG-TDO") (class "Default")
      (node (ref "J17") (pin "1") (pinfunction "1_1") (pintype "passive"))
      (node (ref "J20") (pin "6") (pinfunction "TDO/SWO_6") (pintype "passive"))
      (node (ref "R7") (pin "2") (pinfunction "2_2") (pintype "passive"))
      (node (ref "TP4") (pin "1") (pintype "passive"))
    )
    (net (code "66") (name "/JTAG-TMS") (class "Default")
      (node (ref "J15") (pin "1") (pinfunction "1_1") (pintype "passive"))
      (node (ref "J20") (pin "2") (pinfunction "TMS/SWDIO_2") (pintype "passive"))
      (node (ref "R8") (pin "2") (pinfunction "2_2") (pintype "passive"))
      (node (ref "TP1") (pin "1") (pintype "passive"))
    )
    (net (code "67") (name "/MODUSB-D_n") (class "Default")
      (node (ref "C43") (pin "1") (pinfunction "1_1") (pintype "passive"))
      (node (ref "R27") (pin "1") (pinfunction "1_1") (pintype "passive"))
    )
    (net (code "68") (name "/MODUSB-D_p") (class "Default")
      (node (ref "C44") (pin "1") (pinfunction "1_1") (pintype "passive"))
      (node (ref "R26") (pin "1") (pinfunction "1_1") (pintype "passive"))
    )
    (net (code "69") (name "/QSPI-CLK") (class "Default")
      (node (ref "U1") (pin "6") (pinfunction "CLK_6") (pintype "input"))
      (node (ref "U2") (pin "6") (pinfunction "CLK_6") (pintype "input"))
      (node (ref "U5") (pin "F1") (pinfunction "IO/SCK2/QSPI_CLK_F1") (pintype "bidirectional"))
    )
    (net (code "70") (name "/QSPI-CS0") (class "Default")
      (node (ref "U2") (pin "1") (pinfunction "CS#_1") (pintype "input"))
      (node (ref "U5") (pin "C4") (pinfunction "IO/nCS2(0)_C4") (pintype "bidirectional"))
    )
    (net (code "71") (name "/QSPI-CS1") (class "Default")
      (node (ref "U1") (pin "1") (pinfunction "CS#_1") (pintype "input"))
      (node (ref "U5") (pin "E1") (pinfunction "IO/nCS2(1)/QSPI_nCS_E1") (pintype "bidirectional"))
    )
    (net (code "72") (name "/QSPI-IO0") (class "Default")
      (node (ref "U1") (pin "5") (pinfunction "SI_/_IO0_5") (pintype "bidirectional"))
      (node (ref "U2") (pin "5") (pinfunction "SI_/_IO0_5") (pintype "bidirectional"))
      (node (ref "U5") (pin "D2") (pinfunction "IO/MOSI2/QSPI[0]_D2") (pintype "bidirectional"))
    )
    (net (code "73") (name "/QSPI-IO1") (class "Default")
      (node (ref "U1") (pin "2") (pinfunction "SO_/_IO1_2") (pintype "bidirectional"))
      (node (ref "U2") (pin "2") (pinfunction "SO_/_IO1_2") (pintype "bidirectional"))
      (node (ref "U5") (pin "E2") (pinfunction "IO/MISO2/QSPI[1]_E2") (pintype "bidirectional"))
    )
    (net (code "74") (name "/QSPI-IO2") (class "Default")
      (node (ref "U1") (pin "3") (pinfunction "WP#_/_IO2_3") (pintype "bidirectional"))
      (node (ref "U2") (pin "3") (pinfunction "WP#_/_IO2_3") (pintype "bidirectional"))
      (node (ref "U5") (pin "D1") (pinfunction "IO/WP2/QSPI[2]_D1") (pintype "bidirectional"))
    )
    (net (code "75") (name "/QSPI-IO3") (class "Default")
      (node (ref "U1") (pin "7") (pinfunction "HOLD#¦RESET#_/_IO3_7") (pintype "bidirectional"))
      (node (ref "U2") (pin "7") (pinfunction "HOLD#¦RESET#_/_IO3_7") (pintype "bidirectional"))
      (node (ref "U5") (pin "F2") (pinfunction "IO/HD2/QSPI[3]_F2") (pintype "bidirectional"))
    )
    (net (code "76") (name "/RESETn") (class "Default")
      (node (ref "J20") (pin "10") (pinfunction "nRESET_10") (pintype "passive"))
      (node (ref "R9") (pin "2") (pinfunction "2_2") (pintype "passive"))
      (node (ref "U5") (pin "J3") (pinfunction "nRESET_J3") (pintype "input"))
    )
    (net (code "77") (name "/RMODUSB-D_n") (class "Default")
      (node (ref "R27") (pin "2") (pinfunction "2_2") (pintype "passive"))
      (node (ref "U5") (pin "D9") (pinfunction "D-_D9") (pintype "bidirectional"))
    )
    (net (code "78") (name "/RMODUSB-D_p") (class "Default")
      (node (ref "R26") (pin "2") (pinfunction "2_2") (pintype "passive"))
      (node (ref "U5") (pin "C9") (pinfunction "D+_C9") (pintype "bidirectional"))
    )
    (net (code "79") (name "/XT-32k-n") (class "Default")
      (node (ref "J21") (pin "2") (pinfunction "2_2") (pintype "passive"))
      (node (ref "U5") (pin "B6") (pinfunction "IO/XL2(32kHz_IN)_B6") (pintype "bidirectional"))
    )
    (net (code "80") (name "/XT-32k-p") (class "Default")
      (node (ref "J19") (pin "2") (pinfunction "2_2") (pintype "passive"))
      (node (ref "U5") (pin "C6") (pinfunction "IO/XL1_C6") (pintype "bidirectional"))
    )
    (net (code "84") (name "GND") (class "Default")
      (node (ref "C11") (pin "2") (pinfunction "2_2") (pintype "passive"))
      (node (ref "C12") (pin "2") (pinfunction "2_2") (pintype "passive"))
      (node (ref "C15") (pin "2") (pinfunction "2_2") (pintype "passive"))
      (node (ref "C2") (pin "2") (pinfunction "2_2") (pintype "passive"))
      (node (ref "C24") (pin "2") (pinfunction "2_2") (pintype "passive"))
      (node (ref "C4") (pin "2") (pinfunction "2_2") (pintype "passive"))
      (node (ref "C43") (pin "2") (pinfunction "2_2") (pintype "passive"))
      (node (ref "C44") (pin "2") (pinfunction "2_2") (pintype "passive"))
      (node (ref "C45") (pin "2") (pinfunction "2_2") (pintype "passive"))
      (node (ref "C47") (pin "2") (pinfunction "2_2") (pintype "passive"))
      (node (ref "C5") (pin "2") (pinfunction "2_2") (pintype "passive"))
      (node (ref "C6") (pin "2") (pinfunction "2_2") (pintype "passive"))
      (node (ref "C8") (pin "2") (pinfunction "2_2") (pintype "passive"))
      (node (ref "J12") (pin "2") (pinfunction "2_2") (pintype "power_in"))
      (node (ref "J20") (pin "3") (pinfunction "GND_3") (pintype "passive"))
      (node (ref "J20") (pin "5") (pinfunction "GND_5") (pintype "passive"))
      (node (ref "J20") (pin "9") (pinfunction "GND_9") (pintype "passive"))
      (node (ref "L1") (pin "2") (pinfunction "2_2") (pintype "passive"))
      (node (ref "TP16") (pin "1") (pintype "passive"))
      (node (ref "TP17") (pin "1") (pintype "passive"))
      (node (ref "TP44") (pin "1") (pintype "passive"))
      (node (ref "U1") (pin "4") (pinfunction "GND_4") (pintype "power_in"))
      (node (ref "U2") (pin "4") (pinfunction "GND_4") (pintype "power_in"))
      (node (ref "U5") (pin "A1") (pinfunction "VSS_A1") (pintype "power_in"))
      (node (ref "U5") (pin "A9") (pinfunction "VSS_A9") (pintype "power_in"))
      (node (ref "U5") (pin "B2") (pinfunction "VSS_B2") (pintype "power_in"))
      (node (ref "U5") (pin "B8") (pinfunction "VSS_B8") (pintype "power_in"))
      (node (ref "U5") (pin "E4") (pinfunction "VSS_E4") (pintype "power_in"))
      (node (ref "U5") (pin "E5") (pinfunction "VSS_E5") (pintype "power_in"))
      (node (ref "U5") (pin "F4") (pinfunction "VSS_F4") (pintype "power_in"))
      (node (ref "U5") (pin "F5") (pinfunction "VSS_F5") (pintype "power_in"))
      (node (ref "U5") (pin "K2") (pinfunction "VSS_K2") (pintype "power_in"))
      (node (ref "U5") (pin "K3") (pinfunction "VSS_K3") (pintype "power_in"))
      (node (ref "U5") (pin "K5") (pinfunction "VSS_K5") (pintype "power_in"))
      (node (ref "U5") (pin "K7") (pinfunction "VSS_K7") (pintype "power_in"))
      (node (ref "U5") (pin "K8") (pinfunction "VSS_K8") (pintype "power_in"))
      (node (ref "U5") (pin "L1") (pinfunction "VSS_L1") (pintype "power_in"))
      (node (ref "U5") (pin "L9") (pinfunction "VSS_L9") (pintype "power_in"))
      (node (ref "U5") (pin "M1") (pinfunction "VSS_M1") (pintype "power_in"))
      (node (ref "U5") (pin "M2") (pinfunction "VSS_M2") (pintype "power_in"))
      (node (ref "U5") (pin "M8") (pinfunction "VSS_M8") (pintype "power_in"))
      (node (ref "U5") (pin "M9") (pinfunction "VSS_M9") (pintype "power_in"))
    )
    (net (code "85") (name "Net-(C8-Pad1)") (class "Default")
      (node (ref "C8") (pin "1") (pinfunction "1_1") (pintype "passive"))
      (node (ref "J19") (pin "1") (pinfunction "1_1") (pintype "passive"))
      (node (ref "X1") (pin "2") (pintype "passive"))
    )
    (net (code "86") (name "Net-(C11-Pad1)") (class "Default")
      (node (ref "C11") (pin "1") (pinfunction "1_1") (pintype "passive"))
      (node (ref "J21") (pin "1") (pinfunction "1_1") (pintype "passive"))
      (node (ref "X1") (pin "1") (pintype "passive"))
    )
    (net (code "87") (name "Net-(C42-Pad2)") (class "Default")
      (node (ref "C42") (pin "2") (pinfunction "2_2") (pintype "passive"))
      (node (ref "L1") (pin "1") (pinfunction "1_1") (pintype "passive"))
    )
    (net (code "88") (name "Net-(J12-ANT)") (class "Default")
      (node (ref "C42") (pin "1") (pinfunction "1_1") (pintype "passive"))
      (node (ref "J12") (pin "1") (pinfunction "ANT_1") (pintype "passive"))
      (node (ref "U5") (pin "K9") (pinfunction "ANT1_K9") (pintype "passive"))
    )
    (net (code "89") (name "Net-(U1-VCC)") (class "Default")
      (node (ref "C12") (pin "1") (pinfunction "1_1") (pintype "passive"))
      (node (ref "C45") (pin "1") (pinfunction "1_1") (pintype "passive"))
      (node (ref "R11") (pin "2") (pinfunction "2_2") (pintype "passive"))
      (node (ref "R69") (pin "2") (pinfunction "2_2") (pintype "passive"))
      (node (ref "U1") (pin "8") (pinfunction "VCC_8") (pintype "power_in"))
    )
    (net (code "90") (name "Net-(U2-VCC)") (class "Default")
      (node (ref "C24") (pin "1") (pinfunction "1_1") (pintype "passive"))
      (node (ref "C47") (pin "1") (pinfunction "1_1") (pintype "passive"))
      (node (ref "R70") (pin "2") (pinfunction "2_2") (pintype "passive"))
      (node (ref "R71") (pin "2") (pinfunction "2_2") (pintype "passive"))
      (node (ref "U2") (pin "8") (pinfunction "VCC_8") (pintype "power_in"))
    )
    (net (code "91") (name "VDD") (class "Default")
      (node (ref "C2") (pin "1") (pinfunction "1_1") (pintype "passive"))
      (node (ref "C4") (pin "1") (pinfunction "1_1") (pintype "passive"))
      (node (ref "U5") (pin "A8") (pinfunction "VDDH_A8") (pintype "power_in"))
    )
    (net (code "92") (name "VDD-IO") (class "Default")
      (node (ref "C5") (pin "1") (pinfunction "1_1") (pintype "passive"))
      (node (ref "C6") (pin "1") (pinfunction "1_1") (pintype "passive"))
      (node (ref "U5") (pin "A7") (pinfunction "VDD_A7") (pintype "power_in"))
      (node (ref "U5") (pin "B7") (pinfunction "VDD_B7") (pintype "power_in"))
    )
    (net (code "93") (name "VDD-SPI") (class "Default")
      (node (ref "C15") (pin "1") (pinfunction "1_1") (pintype "passive"))
      (node (ref "R11") (pin "1") (pinfunction "1_1") (pintype "passive"))
      (node (ref "R70") (pin "1") (pinfunction "1_1") (pintype "passive"))
      (node (ref "U5") (pin "J1") (pinfunction "VDD_SPI_J1") (pintype "passive"))
    )
    (net (code "94") (name "unconnected-(J20-KEY-Pad7)") (class "Default")
      (node (ref "J20") (pin "7") (pinfunction "KEY_7") (pintype "passive+no_connect"))
    )
    (net (code "95") (name "unconnected-(U5-ANT2-PadK1)") (class "Default")
      (node (ref "U5") (pin "K1") (pinfunction "ANT2_K1") (pintype "passive+no_connect"))
    )
    (net (code "96") (name "unconnected-(U5-IO-PadA4)") (class "Default")
      (node (ref "U5") (pin "A4") (pinfunction "IO_A4") (pintype "bidirectional+no_connect"))
    )
    (net (code "97") (name "unconnected-(U5-IO-PadD7)") (class "Default")
      (node (ref "U5") (pin "D7") (pinfunction "IO_D7") (pintype "bidirectional+no_connect"))
    )
    (net (code "98") (name "unconnected-(U5-IO-PadJ4)") (class "Default")
      (node (ref "U5") (pin "J4") (pinfunction "IO_J4") (pintype "bidirectional+no_connect"))
    )
    (net (code "99") (name "unconnected-(U5-IO-PadJ5)") (class "Default")
      (node (ref "U5") (pin "J5") (pinfunction "IO_J5") (pintype "bidirectional+no_connect"))
    )
    (net (code "100") (name "unconnected-(U5-IO{slash}NFC1-PadC5)") (class "Default")
      (node (ref "U5") (pin "C5") (pinfunction "IO/NFC1_C5") (pintype "bidirectional+no_connect"))
    )
    (net (code "101") (name "unconnected-(U5-IO{slash}NFC2-PadB5)") (class "Default")
      (node (ref "U5") (pin "B5") (pinfunction "IO/NFC2_B5") (pintype "bidirectional+no_connect"))
    )
    (net (code "102") (name "unconnected-(U5-IO{slash}RF_CTRL1{slash}CTX-PadG5)") (class "Default")
      (node (ref "U5") (pin "G5") (pinfunction "IO/RF_CTRL1/CTX_G5") (pintype "bidirectional+no_connect"))
    )
    (net (code "103") (name "unconnected-(U5-IO{slash}RF_CTRL2{slash}CRX-PadG7)") (class "Default")
      (node (ref "U5") (pin "G7") (pinfunction "IO/RF_CTRL2/CRX_G7") (pintype "bidirectional+no_connect"))
    )
    (net (code "104") (name "unconnected-(U5-IO{slash}RMII_CLK-PadG4)") (class "Default")
      (node (ref "U5") (pin "G4") (pinfunction "IO/RMII_CLK_G4") (pintype "bidirectional+no_connect"))
    )
    (net (code "105") (name "unconnected-(U5-IO{slash}RMII_CRS-PadJ7)") (class "Default")
      (node (ref "U5") (pin "J7") (pinfunction "IO/RMII_CRS_J7") (pintype "bidirectional+no_connect"))
    )
    (net (code "106") (name "unconnected-(U5-VBUS-PadB9)") (class "Default")
      (node (ref "U5") (pin "B9") (pinfunction "VBUS_B9") (pintype "power_in+no_connect"))
    )
  )
)
